# G1Tech-EnergyMonitor04.net
KiCad netlist of a schematic drawn in EAGLE
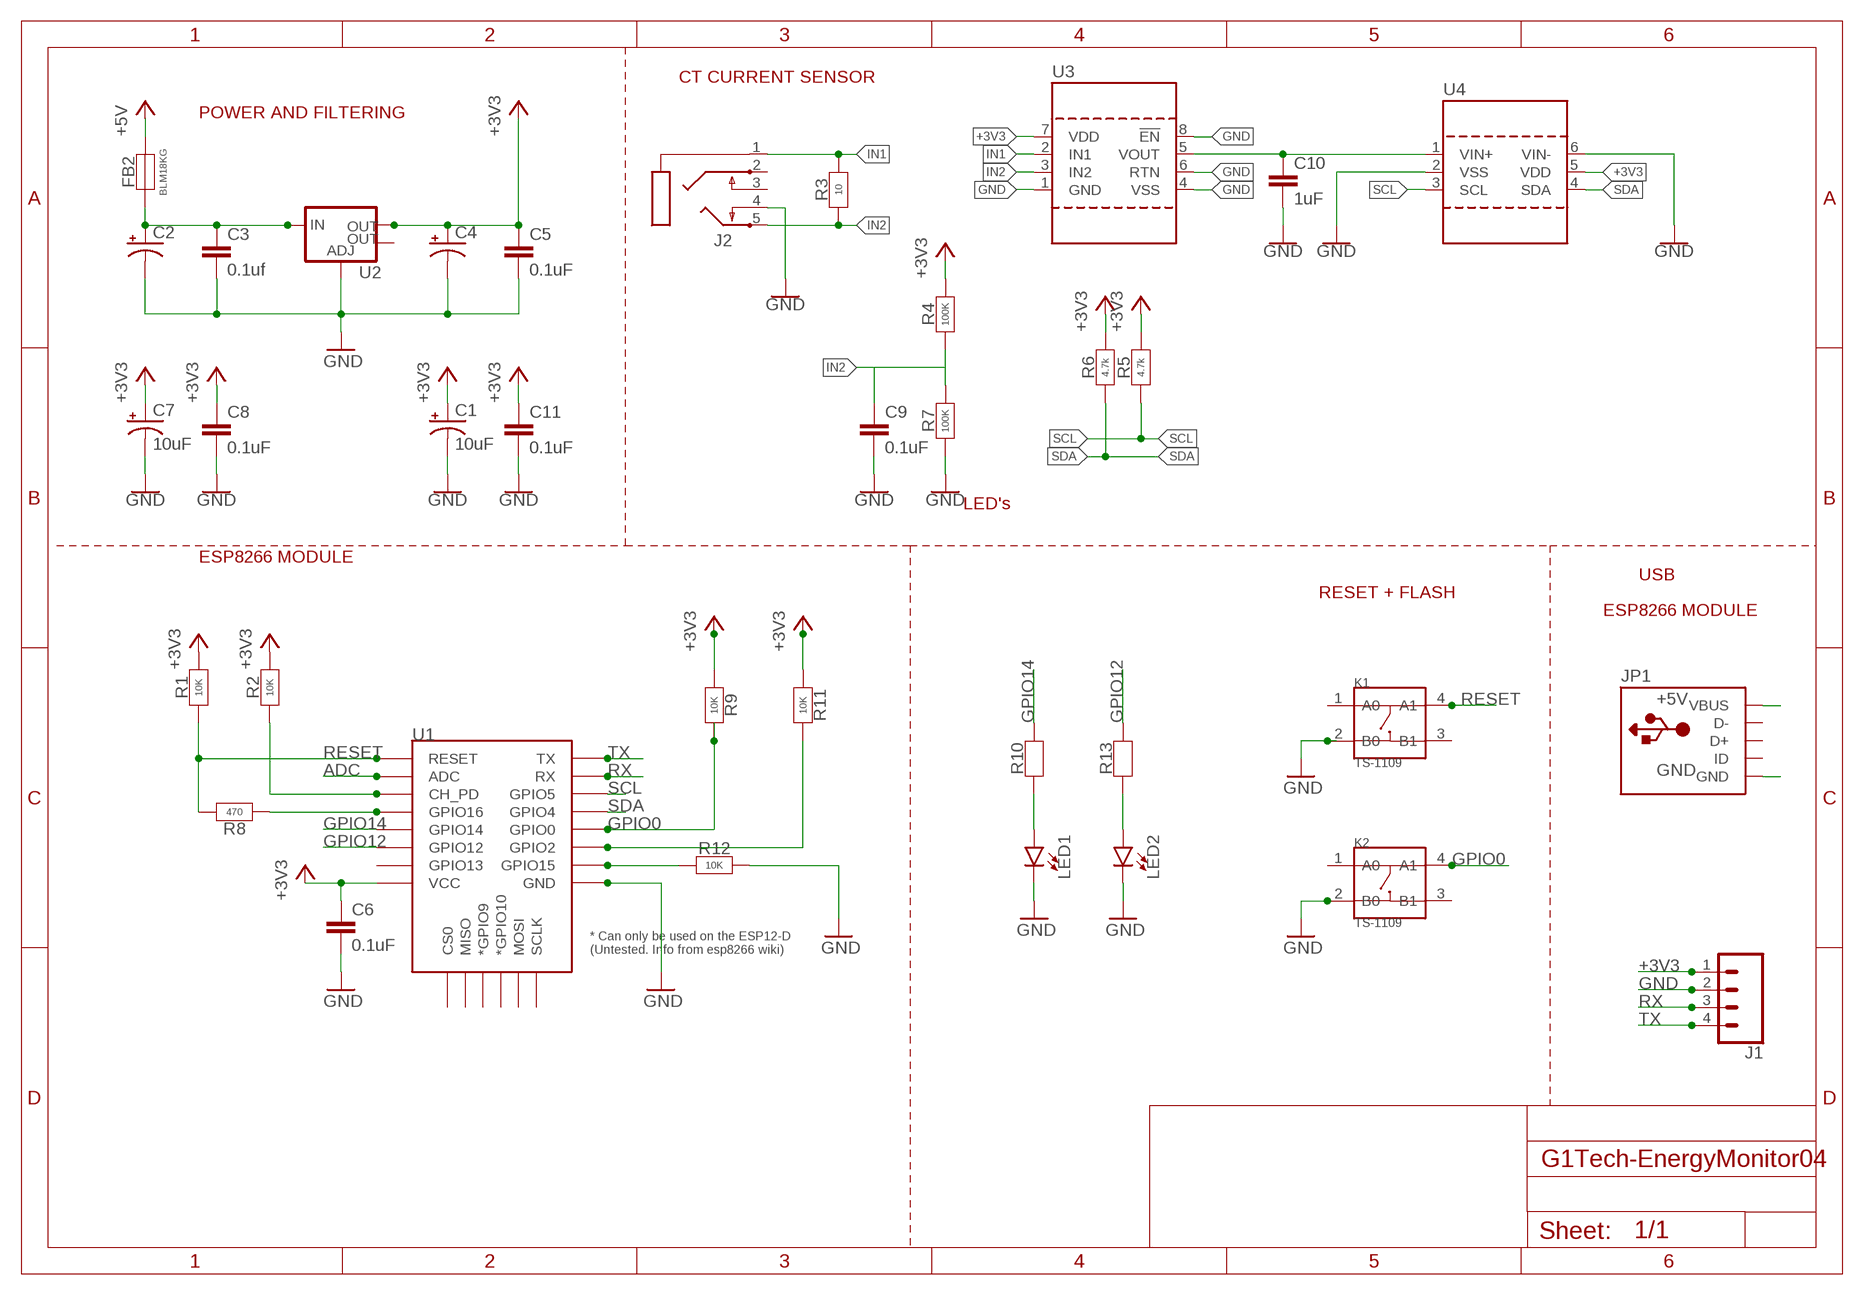
[diagram p0: schematic, sheet 1]

(export (version "E")
  (design (tool "Eeschema 10.0.6"))
  (components
    (comp (ref "C1")
      (value "10uF")
      (footprint "eagle-import:TYPE-A")
      (libsource (lib "eagle-import") (part "C-TYPE-A"))
    )
    (comp (ref "C2")
      (value "C-TYPE-A")
      (footprint "eagle-import:TYPE-A")
      (libsource (lib "eagle-import") (part "C-TYPE-A"))
    )
    (comp (ref "C3")
      (value "0.1uf")
      (footprint "eagle-import:C0805")
      (libsource (lib "eagle-import") (part "C0805"))
    )
    (comp (ref "C4")
      (value "C-TYPE-A")
      (footprint "eagle-import:TYPE-A")
      (libsource (lib "eagle-import") (part "C-TYPE-A"))
    )
    (comp (ref "C5")
      (value "0.1uF")
      (footprint "eagle-import:C0805")
      (libsource (lib "eagle-import") (part "C0805"))
    )
    (comp (ref "C6")
      (value "0.1uF")
      (footprint "eagle-import:C0603")
      (libsource (lib "eagle-import") (part "C0603"))
    )
    (comp (ref "C7")
      (value "10uF")
      (footprint "eagle-import:TYPE-A")
      (libsource (lib "eagle-import") (part "C-TYPE-A"))
    )
    (comp (ref "C8")
      (value "0.1uF")
      (footprint "eagle-import:C0603")
      (libsource (lib "eagle-import") (part "C0603"))
    )
    (comp (ref "C9")
      (value "0.1uF")
      (footprint "eagle-import:C0603")
      (libsource (lib "eagle-import") (part "C0603"))
    )
    (comp (ref "C10")
      (value "1uF")
      (footprint "eagle-import:C0603")
      (libsource (lib "eagle-import") (part "C0603"))
    )
    (comp (ref "C11")
      (value "0.1uF")
      (footprint "eagle-import:C0603")
      (libsource (lib "eagle-import") (part "C0603"))
    )
    (comp (ref "FB2")
      (value "BLM18KG")
      (footprint "eagle-import:FB-0603")
      (libsource (lib "eagle-import") (part "FERRITE-BEAD-0603"))
    )
    (comp (ref "J1")
      (value "CONN_04")
      (footprint "eagle-import:1X04")
      (libsource (lib "eagle-import") (part "CONN_04"))
    )
    (comp (ref "J2")
      (value "PJ-3126-5A")
      (footprint "eagle-import:PJ-3126-5A")
      (libsource (lib "eagle-import") (part "PJ-3126-5A"))
    )
    (comp (ref "JP1")
      (value "USB-MICRO-B-1A")
      (footprint "eagle-import:USB-MICRO")
      (libsource (lib "eagle-import") (part "USB-MICRO-B-1A"))
    )
    (comp (ref "K1")
      (value "TS-1109")
      (footprint "eagle-import:SW4-6.0X6.0X5.0MM")
      (libsource (lib "eagle-import") (part "DIP-BUTTON-4P"))
    )
    (comp (ref "K2")
      (value "TS-1109")
      (footprint "eagle-import:SW4-6.0X6.0X5.0MM")
      (libsource (lib "eagle-import") (part "DIP-BUTTON-4P"))
    )
    (comp (ref "LED1")
      (value "LED0603")
      (footprint "eagle-import:LED0603")
      (libsource (lib "eagle-import") (part "LED0603"))
    )
    (comp (ref "LED2")
      (value "LED0603")
      (footprint "eagle-import:LED0603")
      (libsource (lib "eagle-import") (part "LED0603"))
    )
    (comp (ref "R1")
      (value "10K")
      (footprint "eagle-import:YAGEO-R0603")
      (libsource (lib "eagle-import") (part "YAGEO-R0603"))
    )
    (comp (ref "R2")
      (value "10K")
      (footprint "eagle-import:YAGEO-R0603")
      (libsource (lib "eagle-import") (part "YAGEO-R0603"))
    )
    (comp (ref "R3")
      (value "10")
      (footprint "eagle-import:YAGEO-R0603")
      (libsource (lib "eagle-import") (part "YAGEO-R0603"))
    )
    (comp (ref "R4")
      (value "100K")
      (footprint "eagle-import:YAGEO-R0603")
      (libsource (lib "eagle-import") (part "YAGEO-R0603"))
    )
    (comp (ref "R5")
      (value "4.7k")
      (footprint "eagle-import:YAGEO-R0603")
      (libsource (lib "eagle-import") (part "YAGEO-R0603"))
    )
    (comp (ref "R6")
      (value "4.7k")
      (footprint "eagle-import:YAGEO-R0603")
      (libsource (lib "eagle-import") (part "YAGEO-R0603"))
    )
    (comp (ref "R7")
      (value "100K")
      (footprint "eagle-import:YAGEO-R0603")
      (libsource (lib "eagle-import") (part "YAGEO-R0603"))
    )
    (comp (ref "R8")
      (value "470")
      (footprint "eagle-import:YAGEO-R0603")
      (libsource (lib "eagle-import") (part "YAGEO-R0603"))
    )
    (comp (ref "R9")
      (value "10K")
      (footprint "eagle-import:YAGEO-R0603")
      (libsource (lib "eagle-import") (part "YAGEO-R0603"))
    )
    (comp (ref "R10")
      (value "YAGEO-R0603")
      (footprint "eagle-import:YAGEO-R0603")
      (libsource (lib "eagle-import") (part "YAGEO-R0603"))
    )
    (comp (ref "R11")
      (value "10K")
      (footprint "eagle-import:YAGEO-R0603")
      (libsource (lib "eagle-import") (part "YAGEO-R0603"))
    )
    (comp (ref "R12")
      (value "10K")
      (footprint "eagle-import:YAGEO-R0603")
      (libsource (lib "eagle-import") (part "YAGEO-R0603"))
    )
    (comp (ref "R13")
      (value "YAGEO-R0603")
      (footprint "eagle-import:YAGEO-R0603")
      (libsource (lib "eagle-import") (part "YAGEO-R0603"))
    )
    (comp (ref "U1")
      (value "ESP12ESMD")
      (footprint "eagle-import:ESP12E-SMD")
      (libsource (lib "eagle-import") (part "ESP12ESMD"))
    )
    (comp (ref "U2")
      (value "V_REG_LM1117SOT223")
      (footprint "eagle-import:SOT223")
      (libsource (lib "eagle-import") (part "V_REG_LM1117SOT223"))
    )
    (comp (ref "U3")
      (value "LTC1966")
      (footprint "eagle-import:MS8")
      (libsource (lib "eagle-import") (part "LTC1966"))
    )
    (comp (ref "U4")
      (value "MCP3425")
      (footprint "eagle-import:SOT23-6")
      (libsource (lib "eagle-import") (part "MCP3425"))
    )
  )
  (nets
    (net (code "1") (name "+3V3") (class "Default")
      (node (ref "C1") (pin "A") (pinfunction "A_A") (pintype "passive"))
      (node (ref "C11") (pin "1") (pinfunction "1_1") (pintype "passive"))
      (node (ref "C4") (pin "A") (pinfunction "A_A") (pintype "passive"))
      (node (ref "C5") (pin "1") (pinfunction "1_1") (pintype "passive"))
      (node (ref "C6") (pin "1") (pinfunction "1_1") (pintype "passive"))
      (node (ref "C7") (pin "A") (pinfunction "A_A") (pintype "passive"))
      (node (ref "C8") (pin "1") (pinfunction "1_1") (pintype "passive"))
      (node (ref "J1") (pin "1") (pinfunction "1_1") (pintype "passive"))
      (node (ref "R1") (pin "2") (pinfunction "2_2") (pintype "passive"))
      (node (ref "R11") (pin "1") (pinfunction "1_1") (pintype "passive"))
      (node (ref "R2") (pin "2") (pinfunction "2_2") (pintype "passive"))
      (node (ref "R4") (pin "2") (pinfunction "2_2") (pintype "passive"))
      (node (ref "R5") (pin "2") (pinfunction "2_2") (pintype "passive"))
      (node (ref "R6") (pin "2") (pinfunction "2_2") (pintype "passive"))
      (node (ref "R9") (pin "1") (pinfunction "1_1") (pintype "passive"))
      (node (ref "U1") (pin "VCC") (pinfunction "VCC_VCC") (pintype "bidirectional"))
      (node (ref "U2") (pin "2") (pinfunction "OUT_2") (pintype "output"))
      (node (ref "U3") (pin "7") (pinfunction "VDD_7") (pintype "power_in"))
      (node (ref "U4") (pin "5") (pinfunction "VDD_5") (pintype "power_in"))
    )
    (net (code "2") (name "+5V") (class "Default")
      (node (ref "FB2") (pin "2") (pinfunction "2_2") (pintype "passive"))
      (node (ref "JP1") (pin "VBUS") (pinfunction "VBUS_VBUS") (pintype "power_in"))
    )
    (net (code "3") (name "/ADC") (class "Default")
      (node (ref "U1") (pin "ADC") (pinfunction "ADC_ADC") (pintype "bidirectional"))
    )
    (net (code "4") (name "/GPIO0") (class "Default")
      (node (ref "K2") (pin "4") (pinfunction "A1_4") (pintype "bidirectional"))
      (node (ref "R9") (pin "2") (pinfunction "2_2") (pintype "passive"))
      (node (ref "U1") (pin "GPIO0") (pinfunction "GPIO0_GPIO0") (pintype "bidirectional"))
    )
    (net (code "5") (name "/GPIO12") (class "Default")
      (node (ref "R13") (pin "2") (pinfunction "2_2") (pintype "passive"))
      (node (ref "U1") (pin "GPIO12") (pinfunction "GPIO12_GPIO12") (pintype "bidirectional"))
    )
    (net (code "6") (name "/GPIO14") (class "Default")
      (node (ref "R10") (pin "2") (pinfunction "2_2") (pintype "passive"))
      (node (ref "U1") (pin "GPIO14") (pinfunction "GPIO14_GPIO14") (pintype "bidirectional"))
    )
    (net (code "7") (name "/RESET") (class "Default")
      (node (ref "K1") (pin "4") (pinfunction "A1_4") (pintype "bidirectional"))
      (node (ref "R1") (pin "1") (pinfunction "1_1") (pintype "passive"))
      (node (ref "R8") (pin "2") (pinfunction "2_2") (pintype "passive"))
      (node (ref "U1") (pin "RESET") (pinfunction "RESET_RESET") (pintype "bidirectional"))
    )
    (net (code "8") (name "/RX") (class "Default")
      (node (ref "J1") (pin "3") (pinfunction "3_3") (pintype "passive"))
      (node (ref "U1") (pin "RXD0") (pinfunction "RX_RXD0") (pintype "bidirectional"))
    )
    (net (code "9") (name "/TX") (class "Default")
      (node (ref "J1") (pin "4") (pinfunction "4_4") (pintype "passive"))
      (node (ref "U1") (pin "TXD0") (pinfunction "TX_TXD0") (pintype "bidirectional"))
    )
    (net (code "10") (name "GND") (class "Default")
      (node (ref "C1") (pin "C") (pinfunction "C_C") (pintype "passive"))
      (node (ref "C10") (pin "2") (pinfunction "2_2") (pintype "passive"))
      (node (ref "C11") (pin "2") (pinfunction "2_2") (pintype "passive"))
      (node (ref "C2") (pin "C") (pinfunction "C_C") (pintype "passive"))
      (node (ref "C3") (pin "2") (pinfunction "2_2") (pintype "passive"))
      (node (ref "C4") (pin "C") (pinfunction "C_C") (pintype "passive"))
      (node (ref "C5") (pin "2") (pinfunction "2_2") (pintype "passive"))
      (node (ref "C6") (pin "2") (pinfunction "2_2") (pintype "passive"))
      (node (ref "C7") (pin "C") (pinfunction "C_C") (pintype "passive"))
      (node (ref "C8") (pin "2") (pinfunction "2_2") (pintype "passive"))
      (node (ref "C9") (pin "2") (pinfunction "2_2") (pintype "passive"))
      (node (ref "J1") (pin "2") (pinfunction "2_2") (pintype "passive"))
      (node (ref "J2") (pin "4") (pinfunction "4_4") (pintype "passive"))
      (node (ref "JP1") (pin "GND") (pinfunction "GND_GND") (pintype "power_in"))
      (node (ref "K1") (pin "2") (pinfunction "B0_2") (pintype "bidirectional"))
      (node (ref "K2") (pin "2") (pinfunction "B0_2") (pintype "bidirectional"))
      (node (ref "LED1") (pin "C") (pinfunction "C_C") (pintype "passive"))
      (node (ref "LED2") (pin "C") (pinfunction "C_C") (pintype "passive"))
      (node (ref "R12") (pin "2") (pinfunction "2_2") (pintype "passive"))
      (node (ref "R7") (pin "1") (pinfunction "1_1") (pintype "passive"))
      (node (ref "U1") (pin "GND") (pinfunction "GND_GND") (pintype "bidirectional"))
      (node (ref "U2") (pin "1") (pinfunction "ADJ_1") (pintype "input"))
      (node (ref "U3") (pin "1") (pinfunction "GND_1") (pintype "power_in"))
      (node (ref "U3") (pin "4") (pinfunction "VSS_4") (pintype "power_in"))
      (node (ref "U3") (pin "6") (pinfunction "RTN_6") (pintype "output"))
      (node (ref "U3") (pin "8") (pinfunction "~{EN}_8") (pintype "bidirectional"))
      (node (ref "U4") (pin "2") (pinfunction "VSS_2") (pintype "power_in"))
      (node (ref "U4") (pin "6") (pinfunction "VIN-_6") (pintype "input"))
    )
    (net (code "11") (name "IN1") (class "Default")
      (node (ref "J2") (pin "1") (pinfunction "1_1") (pintype "passive"))
      (node (ref "R3") (pin "2") (pinfunction "2_2") (pintype "passive"))
      (node (ref "U3") (pin "2") (pinfunction "IN1_2") (pintype "input"))
    )
    (net (code "12") (name "IN2") (class "Default")
      (node (ref "C9") (pin "1") (pinfunction "1_1") (pintype "passive"))
      (node (ref "J2") (pin "5") (pinfunction "5_5") (pintype "passive"))
      (node (ref "R3") (pin "1") (pinfunction "1_1") (pintype "passive"))
      (node (ref "R4") (pin "1") (pinfunction "1_1") (pintype "passive"))
      (node (ref "R7") (pin "2") (pinfunction "2_2") (pintype "passive"))
      (node (ref "U3") (pin "3") (pinfunction "IN2_3") (pintype "input"))
    )
    (net (code "13") (name "Net-(LED1-PadA)") (class "Default")
      (node (ref "LED1") (pin "A") (pinfunction "A_A") (pintype "passive"))
      (node (ref "R10") (pin "1") (pinfunction "1_1") (pintype "passive"))
    )
    (net (code "14") (name "Net-(LED2-PadA)") (class "Default")
      (node (ref "LED2") (pin "A") (pinfunction "A_A") (pintype "passive"))
      (node (ref "R13") (pin "1") (pinfunction "1_1") (pintype "passive"))
    )
    (net (code "15") (name "Net-(R2-Pad1)") (class "Default")
      (node (ref "R2") (pin "1") (pinfunction "1_1") (pintype "passive"))
      (node (ref "U1") (pin "CH_PD") (pinfunction "CH_PD_CH_PD") (pintype "bidirectional"))
    )
    (net (code "16") (name "Net-(R8-Pad1)") (class "Default")
      (node (ref "R8") (pin "1") (pinfunction "1_1") (pintype "passive"))
      (node (ref "U1") (pin "GPIO16") (pinfunction "GPIO16_GPIO16") (pintype "bidirectional"))
    )
    (net (code "17") (name "Net-(R11-Pad2)") (class "Default")
      (node (ref "R11") (pin "2") (pinfunction "2_2") (pintype "passive"))
      (node (ref "U1") (pin "GPIO2") (pinfunction "GPIO2_GPIO2") (pintype "bidirectional"))
    )
    (net (code "18") (name "Net-(R12-Pad1)") (class "Default")
      (node (ref "R12") (pin "1") (pinfunction "1_1") (pintype "passive"))
      (node (ref "U1") (pin "GPIO15") (pinfunction "GPIO15_GPIO15") (pintype "bidirectional"))
    )
    (net (code "19") (name "Net-(U2-IN)") (class "Default")
      (node (ref "C2") (pin "A") (pinfunction "A_A") (pintype "passive"))
      (node (ref "C3") (pin "1") (pinfunction "1_1") (pintype "passive"))
      (node (ref "FB2") (pin "1") (pinfunction "1_1") (pintype "passive"))
      (node (ref "U2") (pin "3") (pinfunction "IN_3") (pintype "input"))
    )
    (net (code "20") (name "Net-(U3-VOUT)") (class "Default")
      (node (ref "C10") (pin "1") (pinfunction "1_1") (pintype "passive"))
      (node (ref "U3") (pin "5") (pinfunction "VOUT_5") (pintype "output"))
      (node (ref "U4") (pin "1") (pinfunction "VIN+_1") (pintype "input"))
    )
    (net (code "21") (name "SCL") (class "Default")
      (node (ref "R5") (pin "1") (pinfunction "1_1") (pintype "passive"))
      (node (ref "U1") (pin "GPIO5") (pinfunction "GPIO5_GPIO5") (pintype "bidirectional"))
      (node (ref "U4") (pin "3") (pinfunction "SCL_3") (pintype "bidirectional"))
    )
    (net (code "22") (name "SDA") (class "Default")
      (node (ref "R6") (pin "1") (pinfunction "1_1") (pintype "passive"))
      (node (ref "U1") (pin "GPIO4") (pinfunction "GPIO4_GPIO4") (pintype "bidirectional"))
      (node (ref "U4") (pin "4") (pinfunction "SDA_4") (pintype "bidirectional"))
    )
    (net (code "23") (name "unconnected-(J2-Pad2)") (class "Default")
      (node (ref "J2") (pin "2") (pinfunction "2_2") (pintype "passive"))
    )
    (net (code "24") (name "unconnected-(J2-Pad3)") (class "Default")
      (node (ref "J2") (pin "3") (pinfunction "3_3") (pintype "passive"))
    )
    (net (code "25") (name "unconnected-(JP1-PadD+)") (class "Default")
      (node (ref "JP1") (pin "D+") (pinfunction "D+_D+") (pintype "bidirectional"))
    )
    (net (code "26") (name "unconnected-(JP1-PadD-)") (class "Default")
      (node (ref "JP1") (pin "D-") (pinfunction "D-_D-") (pintype "bidirectional"))
    )
    (net (code "27") (name "unconnected-(JP1-PadID)") (class "Default")
      (node (ref "JP1") (pin "ID") (pinfunction "ID_ID") (pintype "bidirectional"))
    )
    (net (code "28") (name "unconnected-(K1-A0-Pad1)") (class "Default")
      (node (ref "K1") (pin "1") (pinfunction "A0_1") (pintype "bidirectional"))
    )
    (net (code "29") (name "unconnected-(K1-B1-Pad3)") (class "Default")
      (node (ref "K1") (pin "3") (pinfunction "B1_3") (pintype "bidirectional"))
    )
    (net (code "30") (name "unconnected-(K2-A0-Pad1)") (class "Default")
      (node (ref "K2") (pin "1") (pinfunction "A0_1") (pintype "bidirectional"))
    )
    (net (code "31") (name "unconnected-(K2-B1-Pad3)") (class "Default")
      (node (ref "K2") (pin "3") (pinfunction "B1_3") (pintype "bidirectional"))
    )
    (net (code "32") (name "unconnected-(U1-*GPIO9-PadGPIO9)") (class "Default")
      (node (ref "U1") (pin "GPIO9") (pinfunction "*GPIO9_GPIO9") (pintype "bidirectional"))
    )
    (net (code "33") (name "unconnected-(U1-*GPIO10-PadGPIO10)") (class "Default")
      (node (ref "U1") (pin "GPIO10") (pinfunction "*GPIO10_GPIO10") (pintype "bidirectional"))
    )
    (net (code "34") (name "unconnected-(U1-PadCS0)") (class "Default")
      (node (ref "U1") (pin "CS0") (pinfunction "CS0_CS0") (pintype "bidirectional"))
    )
    (net (code "35") (name "unconnected-(U1-PadGPIO13)") (class "Default")
      (node (ref "U1") (pin "GPIO13") (pinfunction "GPIO13_GPIO13") (pintype "bidirectional"))
    )
    (net (code "36") (name "unconnected-(U1-PadMISO)") (class "Default")
      (node (ref "U1") (pin "MISO") (pinfunction "MISO_MISO") (pintype "bidirectional"))
    )
    (net (code "37") (name "unconnected-(U1-PadMOSI)") (class "Default")
      (node (ref "U1") (pin "MOSI") (pinfunction "MOSI_MOSI") (pintype "bidirectional"))
    )
    (net (code "38") (name "unconnected-(U1-PadSCLK)") (class "Default")
      (node (ref "U1") (pin "SCLK") (pinfunction "SCLK_SCLK") (pintype "bidirectional"))
    )
    (net (code "39") (name "unconnected-(U2-OUT-Pad4)") (class "Default")
      (node (ref "U2") (pin "4") (pinfunction "OUT_4") (pintype "output"))
    )
  )
)
